# atmega328P.net
KiCad netlist of a schematic drawn in Altium Designer
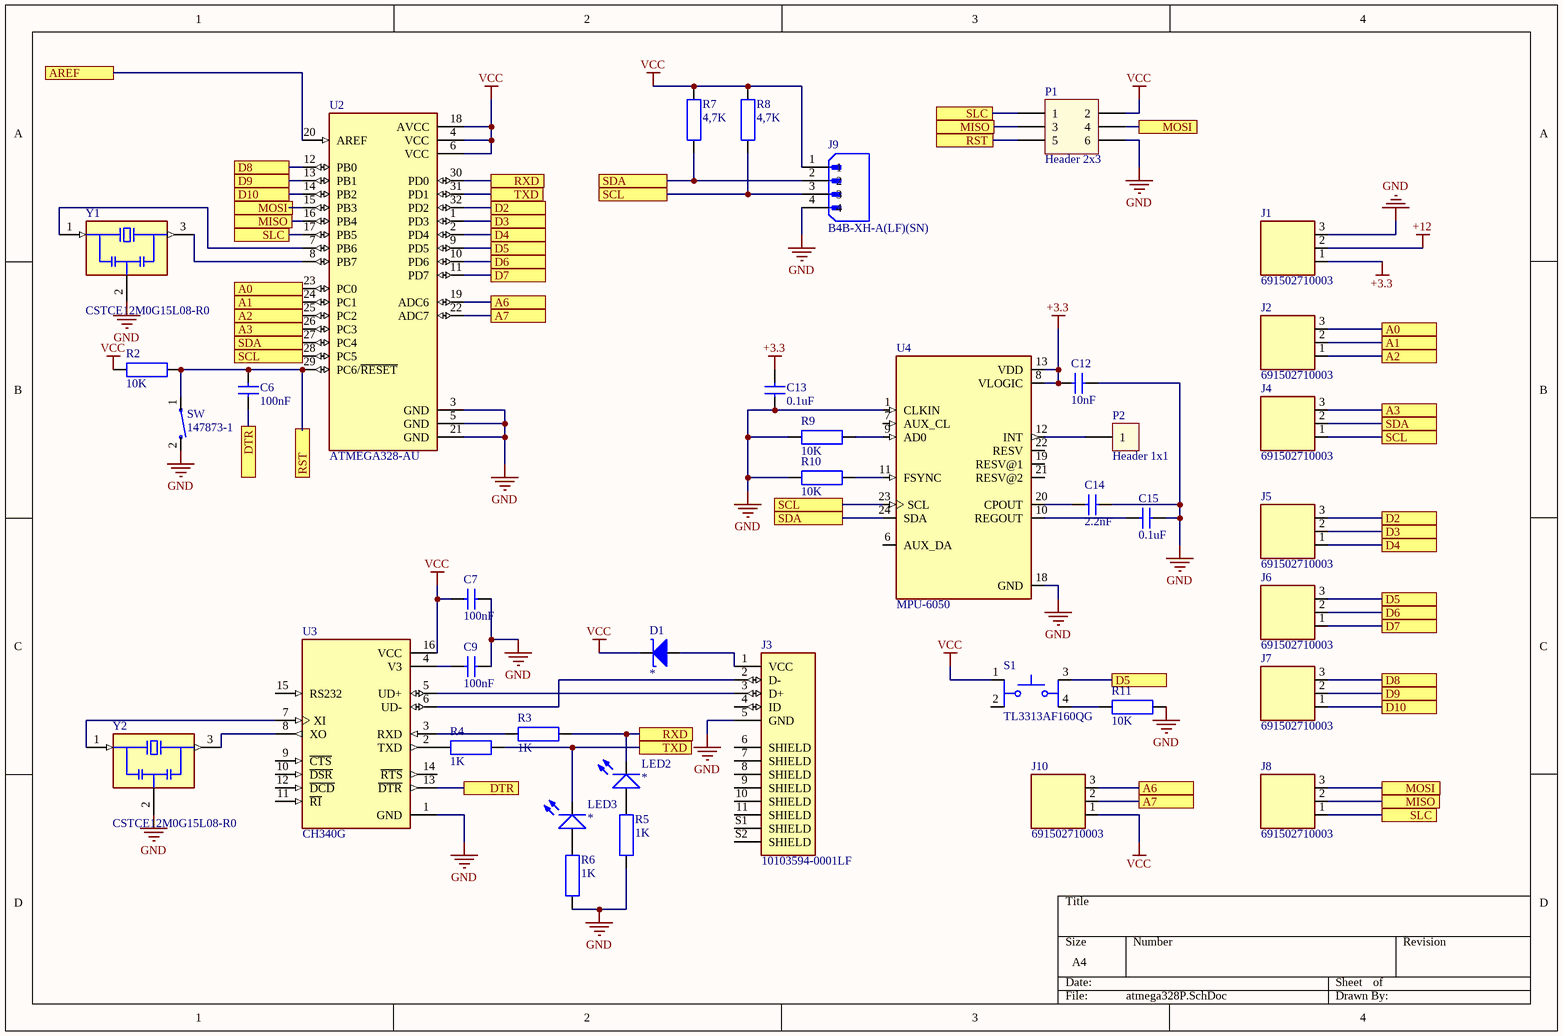
[diagram p0: atmega328P.SchDoc]

(export (version "E")
  (design (tool "Eeschema 10.0.6"))
  (components
    (comp (ref "C6")
      (value "100nF")
      (footprint "SMD_CAPACITOR_0805")
      (description "Capacitor")
      (libsource (lib "VPP_Library") (part "Capacitor"))
    )
    (comp (ref "C7")
      (value "100nF")
      (footprint "SMD_CAPACITOR_0805")
      (description "Capacitor")
      (libsource (lib "VPP_Library") (part "Capacitor"))
    )
    (comp (ref "C9")
      (value "100nF")
      (footprint "SMD_CAPACITOR_0805")
      (description "Capacitor")
      (libsource (lib "VPP_Library") (part "Capacitor"))
    )
    (comp (ref "C12")
      (value "10nF")
      (footprint "SMD_CAPACITOR_0805")
      (description "Capacitor")
      (libsource (lib "VPP_Library") (part "Capacitor"))
    )
    (comp (ref "C13")
      (value "0.1uF")
      (footprint "SMD_CAPACITOR_0805")
      (description "Capacitor")
      (libsource (lib "VPP_Library") (part "Capacitor"))
    )
    (comp (ref "C14")
      (value "2.2nF")
      (footprint "SMD_CAPACITOR_0805")
      (description "Capacitor")
      (libsource (lib "VPP_Library") (part "Capacitor"))
    )
    (comp (ref "C15")
      (value "0.1uF")
      (footprint "SMD_CAPACITOR_0805")
      (description "Capacitor")
      (libsource (lib "VPP_Library") (part "Capacitor"))
    )
    (comp (ref "D1")
      (value "*")
      (footprint "SMD_DO-214AC")
      (description "Diode Schottky")
      (fields (field (name "ALTIUM_VALUE") "*"))
      (libsource (lib "VPP_Library") (part "Diode_Schottky"))
    )
    (comp (ref "J1")
      (value "691502710003")
      (footprint "691502710003")
      (description "3 Position Wire to Board Terminal Block Horizontal with Board 0.197 (5.00mm) Through Hole")
      (fields (field (name "MF") "Wurth Elektronik"))
      (libsource (lib "connector") (part "691502710003"))
    )
    (comp (ref "J2")
      (value "691502710003")
      (footprint "691502710003")
      (description "3 Position Wire to Board Terminal Block Horizontal with Board 0.197 (5.00mm) Through Hole")
      (fields (field (name "MF") "Wurth Elektronik"))
      (libsource (lib "connector") (part "691502710003"))
    )
    (comp (ref "J3")
      (value "10103594-0001LF")
      (footprint "AMPHENOL_10103594-0001LF")
      (description "USB - micro B USB 2.0 Receptacle Connector 5 Position Surface Mount, Right Angle; Through Hole")
      (libsource (lib "10103594-0001LF") (part "10103594-0001LF"))
    )
    (comp (ref "J4")
      (value "691502710003")
      (footprint "691502710003")
      (description "3 Position Wire to Board Terminal Block Horizontal with Board 0.197 (5.00mm) Through Hole")
      (fields (field (name "MF") "Wurth Elektronik"))
      (libsource (lib "connector") (part "691502710003"))
    )
    (comp (ref "J5")
      (value "691502710003")
      (footprint "691502710003")
      (description "3 Position Wire to Board Terminal Block Horizontal with Board 0.197 (5.00mm) Through Hole")
      (fields (field (name "MF") "Wurth Elektronik"))
      (libsource (lib "connector") (part "691502710003"))
    )
    (comp (ref "J6")
      (value "691502710003")
      (footprint "691502710003")
      (description "3 Position Wire to Board Terminal Block Horizontal with Board 0.197 (5.00mm) Through Hole")
      (fields (field (name "MF") "Wurth Elektronik"))
      (libsource (lib "connector") (part "691502710003"))
    )
    (comp (ref "J7")
      (value "691502710003")
      (footprint "691502710003")
      (description "3 Position Wire to Board Terminal Block Horizontal with Board 0.197 (5.00mm) Through Hole")
      (fields (field (name "MF") "Wurth Elektronik"))
      (libsource (lib "connector") (part "691502710003"))
    )
    (comp (ref "J8")
      (value "691502710003")
      (footprint "691502710003")
      (description "3 Position Wire to Board Terminal Block Horizontal with Board 0.197 (5.00mm) Through Hole")
      (fields (field (name "MF") "Wurth Elektronik"))
      (libsource (lib "connector") (part "691502710003"))
    )
    (comp (ref "J9")
      (value "B4B-XH-A(LF)(SN)")
      (footprint "JST_B4B-XH-A(LF)(SN)")
      (description "Connector Header Through Hole 4 position 0.098 (2.50mm)")
      (fields (field (name "MF") "JST Sales"))
      (libsource (lib "B4B-XH-A_LF__SN_") (part "B4B-XH-A(LF)(SN)"))
    )
    (comp (ref "J10")
      (value "691502710003")
      (footprint "691502710003")
      (description "3 Position Wire to Board Terminal Block Horizontal with Board 0.197 (5.00mm) Through Hole")
      (fields (field (name "MF") "Wurth Elektronik"))
      (libsource (lib "connector") (part "691502710003"))
    )
    (comp (ref "LED2")
      (value "*")
      (footprint "SMD_LED_0805")
      (description "LED")
      (fields (field (name "ALTIUM_VALUE") "*"))
      (libsource (lib "VPP_Library") (part "LED"))
    )
    (comp (ref "LED3")
      (value "*")
      (footprint "SMD_LED_0805")
      (description "LED")
      (fields (field (name "ALTIUM_VALUE") "*"))
      (libsource (lib "VPP_Library") (part "LED"))
    )
    (comp (ref "P1")
      (value "Header 2x3")
      (footprint "THT_HEADER_100MIL_2X3_MALE")
      (libsource (lib "VPP_Library") (part "Header_2x3"))
    )
    (comp (ref "P2")
      (value "Header 1x1")
      (footprint "THT_HEADER_100MIL_1X1_MALE")
      (libsource (lib "VPP_Library") (part "Header_1x1"))
    )
    (comp (ref "R2")
      (value "10K")
      (footprint "SMD_RESISTOR_0805")
      (description "Resistor")
      (libsource (lib "VPP_Library") (part "Resistor"))
    )
    (comp (ref "R3")
      (value "1K")
      (footprint "SMD_RESISTOR_0805")
      (description "Resistor")
      (libsource (lib "VPP_Library") (part "Resistor"))
    )
    (comp (ref "R4")
      (value "1K")
      (footprint "SMD_RESISTOR_0805")
      (description "Resistor")
      (libsource (lib "VPP_Library") (part "Resistor"))
    )
    (comp (ref "R5")
      (value "1K")
      (footprint "SMD_RESISTOR_0805")
      (description "Resistor")
      (libsource (lib "VPP_Library") (part "Resistor"))
    )
    (comp (ref "R6")
      (value "1K")
      (footprint "SMD_RESISTOR_0805")
      (description "Resistor")
      (libsource (lib "VPP_Library") (part "Resistor"))
    )
    (comp (ref "R7")
      (value "4,7K")
      (footprint "SMD_RESISTOR_0805")
      (description "Resistor")
      (libsource (lib "VPP_Library") (part "Resistor"))
    )
    (comp (ref "R8")
      (value "4,7K")
      (footprint "SMD_RESISTOR_0805")
      (description "Resistor")
      (libsource (lib "VPP_Library") (part "Resistor"))
    )
    (comp (ref "R9")
      (value "10K")
      (footprint "SMD_RESISTOR_0805")
      (description "Resistor")
      (libsource (lib "VPP_Library") (part "Resistor"))
    )
    (comp (ref "R10")
      (value "10K")
      (footprint "SMD_RESISTOR_0805")
      (description "Resistor")
      (libsource (lib "VPP_Library") (part "Resistor"))
    )
    (comp (ref "R11")
      (value "10K")
      (footprint "SMD_RESISTOR_0805")
      (description "Resistor")
      (libsource (lib "VPP_Library") (part "Resistor"))
    )
    (comp (ref "S1")
      (value "TL3313AF160QG")
      (footprint "SW_TL3313AF160QG")
      (libsource (lib "TL3313AF160QG") (part "TL3313AF160QG"))
    )
    (comp (ref "SW")
      (value "147873-1")
      (footprint "SW_147873-1")
      (description "Switch Tactile OFF (ON) SPST Rectangular Button J-Bend 0.05A 24VDC 1.77N SMD T/R")
      (fields (field (name "MF") "TE Connectivity"))
      (libsource (lib "button2") (part "147873-1"))
    )
    (comp (ref "U2")
      (value "ATMEGA328-AU")
      (footprint "QFP80P900X900X120-32N")
      (description "AVR AVRÂ® ATmega Microcontroller IC 8-Bit 20MHz 32KB (16K x 16) FLASH 32-TQFP (7x7)")
      (fields (field (name "MF") "Microchip"))
      (libsource (lib "ATMEGA328-AU") (part "ATMEGA328-AU"))
    )
    (comp (ref "U3")
      (value "CH340G")
      (footprint "SOIC127P600X180-16N")
      (description "USB Interface Integrated Circuit")
      (fields (field (name "MP") "Ch340G") (field (name "MF") "WCH"))
      (libsource (lib "CH340G (2)") (part "CH340G"))
    )
    (comp (ref "U4")
      (value "MPU-6050")
      (footprint "QFN50P400X400X95-24N")
      (description "MPU-6050 series Accelerometer, Gyroscope, 3 Axis Sensor Evaluation Board")
      (fields (field (name "MF") "TDK InvenSense"))
      (libsource (lib "MPU-6050") (part "MPU-6050"))
    )
    (comp (ref "Y1")
      (value "CSTCE12M0G15L08-R0")
      (footprint "OSC_CSTCE12M0G15L08-R0")
      (description "CSTCE Series 12 MHz 3.2 x 1.3 x 0.7 mm Built-in Capacitor SMT Resonator")
      (fields (field (name "MF") "Murata"))
      (libsource (lib "CSTCE12M0G15L08-R0") (part "CSTCE12M0G15L08-R0"))
    )
    (comp (ref "Y2")
      (value "CSTCE12M0G15L08-R0")
      (footprint "OSC_CSTCE12M0G15L08-R0")
      (description "CSTCE Series 12 MHz 3.2 x 1.3 x 0.7 mm Built-in Capacitor SMT Resonator")
      (fields (field (name "MF") "Murata"))
      (libsource (lib "CSTCE12M0G15L08-R0") (part "CSTCE12M0G15L08-R0"))
    )
  )
  (nets
    (net (code "1") (name "+3.3") (class "Default")
      (node (ref "C12") (pin "2") (pinfunction "2_2") (pintype "passive"))
      (node (ref "C13") (pin "2") (pinfunction "2_2") (pintype "passive"))
      (node (ref "J1") (pin "1") (pinfunction "1_1") (pintype "passive"))
      (node (ref "U4") (pin "13") (pinfunction "VDD_13") (pintype "power_in"))
      (node (ref "U4") (pin "8") (pinfunction "VLOGIC_8") (pintype "power_in"))
    )
    (net (code "2") (name "+12") (class "Default")
      (node (ref "J1") (pin "2") (pinfunction "2_2") (pintype "passive"))
    )
    (net (code "3") (name "/A0") (class "Default")
      (node (ref "J2") (pin "3") (pinfunction "3_3") (pintype "passive"))
      (node (ref "U2") (pin "23") (pinfunction "PC0_23") (pintype "bidirectional"))
    )
    (net (code "4") (name "/A1") (class "Default")
      (node (ref "J2") (pin "2") (pinfunction "2_2") (pintype "passive"))
      (node (ref "U2") (pin "24") (pinfunction "PC1_24") (pintype "bidirectional"))
    )
    (net (code "5") (name "/A2") (class "Default")
      (node (ref "J2") (pin "1") (pinfunction "1_1") (pintype "passive"))
      (node (ref "U2") (pin "25") (pinfunction "PC2_25") (pintype "bidirectional"))
    )
    (net (code "6") (name "/A3") (class "Default")
      (node (ref "J4") (pin "3") (pinfunction "3_3") (pintype "passive"))
      (node (ref "U2") (pin "26") (pinfunction "PC3_26") (pintype "bidirectional"))
    )
    (net (code "7") (name "/A6") (class "Default")
      (node (ref "J10") (pin "3") (pinfunction "3_3") (pintype "passive"))
      (node (ref "U2") (pin "19") (pinfunction "ADC6_19") (pintype "bidirectional"))
    )
    (net (code "8") (name "/A7") (class "Default")
      (node (ref "J10") (pin "2") (pinfunction "2_2") (pintype "passive"))
      (node (ref "U2") (pin "22") (pinfunction "ADC7_22") (pintype "bidirectional"))
    )
    (net (code "9") (name "/AREF") (class "Default")
      (node (ref "U2") (pin "20") (pinfunction "AREF_20") (pintype "input"))
    )
    (net (code "10") (name "/D2") (class "Default")
      (node (ref "J5") (pin "3") (pinfunction "3_3") (pintype "passive"))
      (node (ref "U2") (pin "32") (pinfunction "PD2_32") (pintype "bidirectional"))
    )
    (net (code "11") (name "/D3") (class "Default")
      (node (ref "J5") (pin "2") (pinfunction "2_2") (pintype "passive"))
      (node (ref "U2") (pin "1") (pinfunction "PD3_1") (pintype "bidirectional"))
    )
    (net (code "12") (name "/D4") (class "Default")
      (node (ref "J5") (pin "1") (pinfunction "1_1") (pintype "passive"))
      (node (ref "U2") (pin "2") (pinfunction "PD4_2") (pintype "bidirectional"))
    )
    (net (code "13") (name "/D5") (class "Default")
      (node (ref "J6") (pin "3") (pinfunction "3_3") (pintype "passive"))
      (node (ref "S1") (pin "3") (pinfunction "3_3") (pintype "passive"))
      (node (ref "U2") (pin "9") (pinfunction "PD5_9") (pintype "bidirectional"))
    )
    (net (code "14") (name "/D6") (class "Default")
      (node (ref "J6") (pin "2") (pinfunction "2_2") (pintype "passive"))
      (node (ref "U2") (pin "10") (pinfunction "PD6_10") (pintype "bidirectional"))
    )
    (net (code "15") (name "/D7") (class "Default")
      (node (ref "J6") (pin "1") (pinfunction "1_1") (pintype "passive"))
      (node (ref "U2") (pin "11") (pinfunction "PD7_11") (pintype "bidirectional"))
    )
    (net (code "16") (name "/D8") (class "Default")
      (node (ref "J7") (pin "3") (pinfunction "3_3") (pintype "passive"))
      (node (ref "U2") (pin "12") (pinfunction "PB0_12") (pintype "bidirectional"))
    )
    (net (code "17") (name "/D9") (class "Default")
      (node (ref "J7") (pin "2") (pinfunction "2_2") (pintype "passive"))
      (node (ref "U2") (pin "13") (pinfunction "PB1_13") (pintype "bidirectional"))
    )
    (net (code "18") (name "/D10") (class "Default")
      (node (ref "J7") (pin "1") (pinfunction "1_1") (pintype "passive"))
      (node (ref "U2") (pin "14") (pinfunction "PB2_14") (pintype "bidirectional"))
    )
    (net (code "19") (name "/DTR") (class "Default")
      (node (ref "C6") (pin "2") (pinfunction "2_2") (pintype "passive"))
      (node (ref "U3") (pin "13") (pinfunction "~{DTR}_13") (pintype "output"))
    )
    (net (code "20") (name "/MISO") (class "Default")
      (node (ref "J8") (pin "2") (pinfunction "2_2") (pintype "passive"))
      (node (ref "P1") (pin "3") (pinfunction "3_3") (pintype "passive"))
      (node (ref "U2") (pin "16") (pinfunction "PB4_16") (pintype "bidirectional"))
    )
    (net (code "21") (name "/MOSI") (class "Default")
      (node (ref "J8") (pin "3") (pinfunction "3_3") (pintype "passive"))
      (node (ref "P1") (pin "4") (pinfunction "4_4") (pintype "passive"))
      (node (ref "U2") (pin "15") (pinfunction "PB3_15") (pintype "bidirectional"))
    )
    (net (code "22") (name "/RST") (class "Default")
      (node (ref "C6") (pin "1") (pinfunction "1_1") (pintype "passive"))
      (node (ref "P1") (pin "5") (pinfunction "5_5") (pintype "passive"))
      (node (ref "R2") (pin "2") (pinfunction "2_2") (pintype "passive"))
      (node (ref "SW") (pin "1") (pinfunction "1_1") (pintype "passive"))
      (node (ref "U2") (pin "29") (pinfunction "PC6/~{RESET}_29") (pintype "bidirectional"))
    )
    (net (code "23") (name "/RXD") (class "Default")
      (node (ref "LED2") (pin "2") (pinfunction "2_2") (pintype "passive"))
      (node (ref "R3") (pin "2") (pinfunction "2_2") (pintype "passive"))
      (node (ref "U2") (pin "30") (pinfunction "PD0_30") (pintype "bidirectional"))
    )
    (net (code "24") (name "/SCL") (class "Default")
      (node (ref "J4") (pin "1") (pinfunction "1_1") (pintype "passive"))
      (node (ref "J9") (pin "3") (pinfunction "3_3") (pintype "passive"))
      (node (ref "R8") (pin "2") (pinfunction "2_2") (pintype "passive"))
      (node (ref "U2") (pin "28") (pinfunction "PC5_28") (pintype "bidirectional"))
      (node (ref "U4") (pin "23") (pinfunction "SCL_23") (pintype "input"))
    )
    (net (code "25") (name "/SDA") (class "Default")
      (node (ref "J4") (pin "2") (pinfunction "2_2") (pintype "passive"))
      (node (ref "J9") (pin "2") (pinfunction "2_2") (pintype "passive"))
      (node (ref "R7") (pin "2") (pinfunction "2_2") (pintype "passive"))
      (node (ref "U2") (pin "27") (pinfunction "PC4_27") (pintype "bidirectional"))
      (node (ref "U4") (pin "24") (pinfunction "SDA_24") (pintype "bidirectional"))
    )
    (net (code "26") (name "/SLC") (class "Default")
      (node (ref "J8") (pin "1") (pinfunction "1_1") (pintype "passive"))
      (node (ref "P1") (pin "1") (pinfunction "1_1") (pintype "passive"))
      (node (ref "U2") (pin "17") (pinfunction "PB5_17") (pintype "bidirectional"))
    )
    (net (code "27") (name "/TXD") (class "Default")
      (node (ref "LED3") (pin "2") (pinfunction "2_2") (pintype "passive"))
      (node (ref "R4") (pin "2") (pinfunction "2_2") (pintype "passive"))
      (node (ref "U2") (pin "31") (pinfunction "PD1_31") (pintype "bidirectional"))
    )
    (net (code "28") (name "GND") (class "Default")
      (node (ref "C12") (pin "1") (pinfunction "1_1") (pintype "passive"))
      (node (ref "C13") (pin "1") (pinfunction "1_1") (pintype "passive"))
      (node (ref "C14") (pin "1") (pinfunction "1_1") (pintype "passive"))
      (node (ref "C15") (pin "1") (pinfunction "1_1") (pintype "passive"))
      (node (ref "C7") (pin "1") (pinfunction "1_1") (pintype "passive"))
      (node (ref "C9") (pin "1") (pinfunction "1_1") (pintype "passive"))
      (node (ref "J1") (pin "3") (pinfunction "3_3") (pintype "passive"))
      (node (ref "J3") (pin "5") (pinfunction "GND_5") (pintype "power_in"))
      (node (ref "J9") (pin "4") (pinfunction "4_4") (pintype "passive"))
      (node (ref "P1") (pin "6") (pinfunction "6_6") (pintype "passive"))
      (node (ref "R10") (pin "1") (pinfunction "1_1") (pintype "passive"))
      (node (ref "R11") (pin "2") (pinfunction "2_2") (pintype "passive"))
      (node (ref "R5") (pin "2") (pinfunction "2_2") (pintype "passive"))
      (node (ref "R6") (pin "1") (pinfunction "1_1") (pintype "passive"))
      (node (ref "R9") (pin "1") (pinfunction "1_1") (pintype "passive"))
      (node (ref "SW") (pin "2") (pinfunction "2_2") (pintype "passive"))
      (node (ref "U2") (pin "21") (pinfunction "GND_21") (pintype "power_in"))
      (node (ref "U2") (pin "3") (pinfunction "GND_3") (pintype "power_in"))
      (node (ref "U2") (pin "5") (pinfunction "GND_5") (pintype "power_in"))
      (node (ref "U3") (pin "1") (pinfunction "GND_1") (pintype "power_in"))
      (node (ref "U4") (pin "1") (pinfunction "CLKIN_1") (pintype "input"))
      (node (ref "U4") (pin "18") (pinfunction "GND_18") (pintype "power_in"))
      (node (ref "Y1") (pin "2") (pinfunction "GND_2") (pintype "power_in"))
      (node (ref "Y2") (pin "2") (pinfunction "GND_2") (pintype "power_in"))
    )
    (net (code "29") (name "Net-(J3-D+)") (class "Default")
      (node (ref "J3") (pin "3") (pinfunction "D+_3") (pintype "bidirectional"))
      (node (ref "U3") (pin "5") (pinfunction "UD+_5") (pintype "bidirectional"))
    )
    (net (code "30") (name "Net-(J3-D-)") (class "Default")
      (node (ref "J3") (pin "2") (pinfunction "D-_2") (pintype "bidirectional"))
      (node (ref "U3") (pin "6") (pinfunction "UD-_6") (pintype "bidirectional"))
    )
    (net (code "31") (name "Net-(J3-VCC)") (class "Default")
      (node (ref "D1") (pin "1") (pinfunction "1_1") (pintype "passive"))
      (node (ref "J3") (pin "1") (pinfunction "VCC_1") (pintype "power_in"))
    )
    (net (code "32") (name "Net-(LED2-Pad1)") (class "Default")
      (node (ref "LED2") (pin "1") (pinfunction "1_1") (pintype "passive"))
      (node (ref "R5") (pin "1") (pinfunction "1_1") (pintype "passive"))
    )
    (net (code "33") (name "Net-(LED3-Pad1)") (class "Default")
      (node (ref "LED3") (pin "1") (pinfunction "1_1") (pintype "passive"))
      (node (ref "R6") (pin "2") (pinfunction "2_2") (pintype "passive"))
    )
    (net (code "34") (name "Net-(R11-Pad1)") (class "Default")
      (node (ref "R11") (pin "1") (pinfunction "1_1") (pintype "passive"))
      (node (ref "S1") (pin "4") (pinfunction "4_4") (pintype "passive"))
    )
    (net (code "35") (name "Net-(U2-PB6)") (class "Default")
      (node (ref "U2") (pin "7") (pinfunction "PB6_7") (pintype "bidirectional"))
      (node (ref "Y1") (pin "1") (pinfunction "IN_1") (pintype "input"))
    )
    (net (code "36") (name "Net-(U2-PB7)") (class "Default")
      (node (ref "U2") (pin "8") (pinfunction "PB7_8") (pintype "bidirectional"))
      (node (ref "Y1") (pin "3") (pinfunction "OUT_3") (pintype "output"))
    )
    (net (code "37") (name "Net-(U3-RXD)") (class "Default")
      (node (ref "R3") (pin "1") (pinfunction "1_1") (pintype "passive"))
      (node (ref "U3") (pin "3") (pinfunction "RXD_3") (pintype "input"))
    )
    (net (code "38") (name "Net-(U3-TXD)") (class "Default")
      (node (ref "R4") (pin "1") (pinfunction "1_1") (pintype "passive"))
      (node (ref "U3") (pin "2") (pinfunction "TXD_2") (pintype "output"))
    )
    (net (code "39") (name "Net-(U3-V3)") (class "Default")
      (node (ref "C9") (pin "2") (pinfunction "2_2") (pintype "passive"))
      (node (ref "U3") (pin "4") (pinfunction "V3_4") (pintype "power_in"))
    )
    (net (code "40") (name "Net-(U3-XI)") (class "Default")
      (node (ref "U3") (pin "7") (pinfunction "XI_7") (pintype "input"))
      (node (ref "Y2") (pin "1") (pinfunction "IN_1") (pintype "input"))
    )
    (net (code "41") (name "Net-(U3-XO)") (class "Default")
      (node (ref "U3") (pin "8") (pinfunction "XO_8") (pintype "output"))
      (node (ref "Y2") (pin "3") (pinfunction "OUT_3") (pintype "output"))
    )
    (net (code "42") (name "Net-(U4-AD0)") (class "Default")
      (node (ref "R9") (pin "2") (pinfunction "2_2") (pintype "passive"))
      (node (ref "U4") (pin "9") (pinfunction "AD0_9") (pintype "input"))
    )
    (net (code "43") (name "Net-(U4-CPOUT)") (class "Default")
      (node (ref "C14") (pin "2") (pinfunction "2_2") (pintype "passive"))
      (node (ref "U4") (pin "20") (pinfunction "CPOUT_20") (pintype "passive"))
    )
    (net (code "44") (name "Net-(U4-FSYNC)") (class "Default")
      (node (ref "R10") (pin "2") (pinfunction "2_2") (pintype "passive"))
      (node (ref "U4") (pin "11") (pinfunction "FSYNC_11") (pintype "input"))
    )
    (net (code "45") (name "Net-(U4-INT)") (class "Default")
      (node (ref "P2") (pin "1") (pinfunction "1_1") (pintype "passive"))
      (node (ref "U4") (pin "12") (pinfunction "INT_12") (pintype "output"))
    )
    (net (code "46") (name "Net-(U4-REGOUT)") (class "Default")
      (node (ref "C15") (pin "2") (pinfunction "2_2") (pintype "passive"))
      (node (ref "U4") (pin "10") (pinfunction "REGOUT_10") (pintype "passive"))
    )
    (net (code "47") (name "VCC") (class "Default")
      (node (ref "C7") (pin "2") (pinfunction "2_2") (pintype "passive"))
      (node (ref "D1") (pin "2") (pinfunction "2_2") (pintype "passive"))
      (node (ref "J10") (pin "1") (pinfunction "1_1") (pintype "passive"))
      (node (ref "J9") (pin "1") (pinfunction "1_1") (pintype "passive"))
      (node (ref "P1") (pin "2") (pinfunction "2_2") (pintype "passive"))
      (node (ref "R2") (pin "1") (pinfunction "1_1") (pintype "passive"))
      (node (ref "R7") (pin "1") (pinfunction "1_1") (pintype "passive"))
      (node (ref "R8") (pin "1") (pinfunction "1_1") (pintype "passive"))
      (node (ref "S1") (pin "1") (pinfunction "1_1") (pintype "passive"))
      (node (ref "U2") (pin "18") (pinfunction "AVCC_18") (pintype "power_in"))
      (node (ref "U2") (pin "4") (pinfunction "VCC_4") (pintype "power_in"))
      (node (ref "U2") (pin "6") (pinfunction "VCC_6") (pintype "power_in"))
      (node (ref "U3") (pin "16") (pinfunction "VCC_16") (pintype "power_in"))
    )
    (net (code "48") (name "unconnected-(J3-ID-Pad4)") (class "Default")
      (node (ref "J3") (pin "4") (pinfunction "ID_4") (pintype "bidirectional"))
    )
    (net (code "49") (name "unconnected-(J3-SHIELD-Pad6)") (class "Default")
      (node (ref "J3") (pin "6") (pinfunction "SHIELD_6") (pintype "passive"))
    )
    (net (code "50") (name "unconnected-(J3-SHIELD-Pad7)") (class "Default")
      (node (ref "J3") (pin "7") (pinfunction "SHIELD_7") (pintype "passive"))
    )
    (net (code "51") (name "unconnected-(J3-SHIELD-Pad8)") (class "Default")
      (node (ref "J3") (pin "8") (pinfunction "SHIELD_8") (pintype "passive"))
    )
    (net (code "52") (name "unconnected-(J3-SHIELD-Pad9)") (class "Default")
      (node (ref "J3") (pin "9") (pinfunction "SHIELD_9") (pintype "passive"))
    )
    (net (code "53") (name "unconnected-(J3-SHIELD-Pad10)") (class "Default")
      (node (ref "J3") (pin "10") (pinfunction "SHIELD_10") (pintype "passive"))
    )
    (net (code "54") (name "unconnected-(J3-SHIELD-Pad11)") (class "Default")
      (node (ref "J3") (pin "11") (pinfunction "SHIELD_11") (pintype "passive"))
    )
    (net (code "55") (name "unconnected-(J3-SHIELD-PadS1)") (class "Default")
      (node (ref "J3") (pin "S1") (pinfunction "SHIELD_S1") (pintype "passive"))
    )
    (net (code "56") (name "unconnected-(J3-SHIELD-PadS2)") (class "Default")
      (node (ref "J3") (pin "S2") (pinfunction "SHIELD_S2") (pintype "passive"))
    )
    (net (code "57") (name "unconnected-(S1-Pad2)") (class "Default")
      (node (ref "S1") (pin "2") (pinfunction "2_2") (pintype "passive"))
    )
    (net (code "58") (name "unconnected-(U3-RS232-Pad15)") (class "Default")
      (node (ref "U3") (pin "15") (pinfunction "RS232_15") (pintype "input"))
    )
    (net (code "59") (name "unconnected-(U3-~{CTS}-Pad9)") (class "Default")
      (node (ref "U3") (pin "9") (pinfunction "~{CTS}_9") (pintype "input"))
    )
    (net (code "60") (name "unconnected-(U3-~{DCD}-Pad12)") (class "Default")
      (node (ref "U3") (pin "12") (pinfunction "~{DCD}_12") (pintype "input"))
    )
    (net (code "61") (name "unconnected-(U3-~{DSR}-Pad10)") (class "Default")
      (node (ref "U3") (pin "10") (pinfunction "~{DSR}_10") (pintype "input"))
    )
    (net (code "62") (name "unconnected-(U3-~{RI}-Pad11)") (class "Default")
      (node (ref "U3") (pin "11") (pinfunction "~{RI}_11") (pintype "input"))
    )
    (net (code "63") (name "unconnected-(U3-~{RTS}-Pad14)") (class "Default")
      (node (ref "U3") (pin "14") (pinfunction "~{RTS}_14") (pintype "output"))
    )
    (net (code "64") (name "unconnected-(U4-AUX_CL-Pad7)") (class "Default")
      (node (ref "U4") (pin "7") (pinfunction "AUX_CL_7") (pintype "input"))
    )
    (net (code "65") (name "unconnected-(U4-AUX_DA-Pad6)") (class "Default")
      (node (ref "U4") (pin "6") (pinfunction "AUX_DA_6") (pintype "bidirectional"))
    )
    (net (code "66") (name "unconnected-(U4-RESV-Pad22)") (class "Default")
      (node (ref "U4") (pin "22") (pinfunction "RESV_22") (pintype "passive"))
    )
    (net (code "67") (name "unconnected-(U4-RESV@1-Pad19)") (class "Default")
      (node (ref "U4") (pin "19") (pinfunction "RESV@1_19") (pintype "passive"))
    )
    (net (code "68") (name "unconnected-(U4-RESV@2-Pad21)") (class "Default")
      (node (ref "U4") (pin "21") (pinfunction "RESV@2_21") (pintype "passive"))
    )
  )
)
